# CSPS.net
KiCad netlist of a schematic drawn in Altium Designer
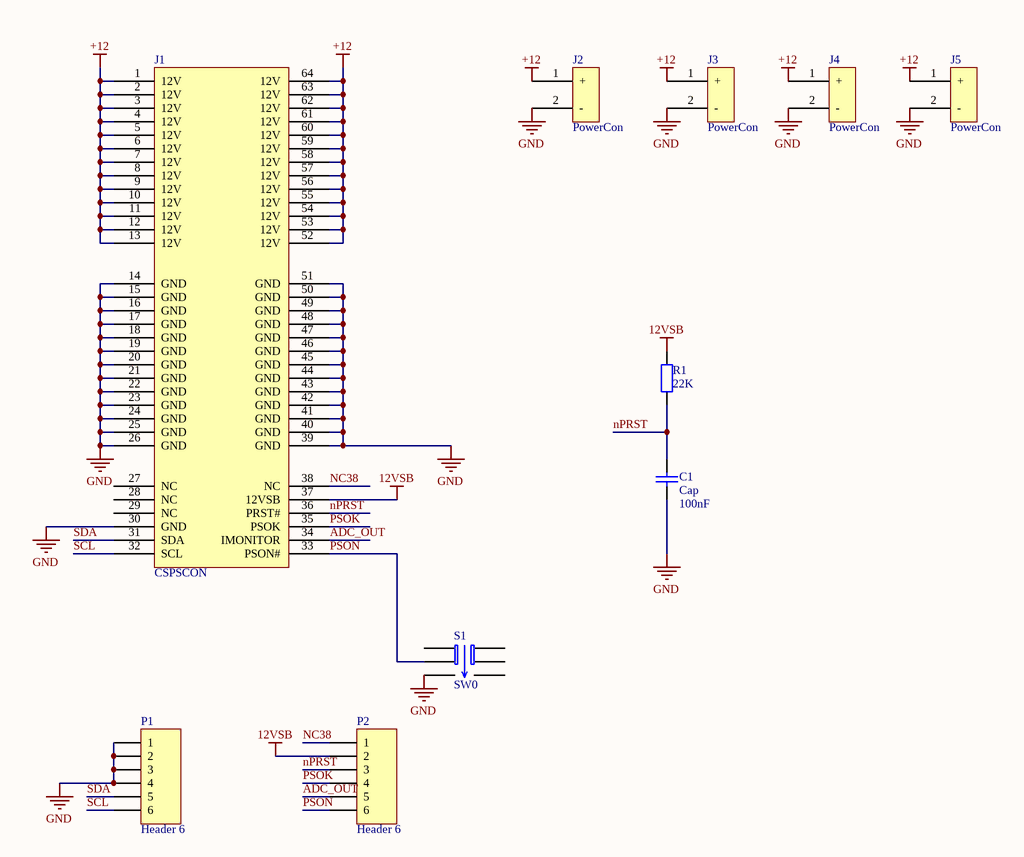
[diagram p0: CSPS.SchDoc]

(export (version "E")
  (design (tool "Eeschema 10.0.6"))
  (components
    (comp (ref "C1")
      (value "Cap")
      (footprint "0402")
      (description "Capacitor")
      (fields (field (name "ALTIUM_VALUE") "100nF") (field (name "PUBLISHER") "Altium Limited"))
      (libsource (lib "Miscellaneous Devices") (part "Cap"))
    )
    (comp (ref "J1")
      (value "CSPSCON")
      (footprint "CSPSCON2")
      (description "2.54 x 64Pin Common Slot Power Supply Connector")
      (libsource (lib "biwefc") (part "CSPSCON"))
    )
    (comp (ref "J2")
      (value "PowerCon")
      (footprint "XT60PB")
      (description "2 Pin Power Connector")
      (libsource (lib "biwefc") (part "PowerCon"))
    )
    (comp (ref "J3")
      (value "PowerCon")
      (footprint "XT60PB")
      (description "2 Pin Power Connector")
      (libsource (lib "biwefc") (part "PowerCon"))
    )
    (comp (ref "J4")
      (value "PowerCon")
      (footprint "XT60PB")
      (description "2 Pin Power Connector")
      (libsource (lib "biwefc") (part "PowerCon"))
    )
    (comp (ref "J5")
      (value "PowerCon")
      (footprint "XT60PB")
      (description "2 Pin Power Connector")
      (libsource (lib "biwefc") (part "PowerCon"))
    )
    (comp (ref "P1")
      (value "Header 6")
      (footprint "HDR1X6")
      (description "Header, 6-Pin")
      (fields (field (name "PUBLISHER") "Altium Limited"))
      (libsource (lib "Miscellaneous Connectors") (part "Header 6"))
    )
    (comp (ref "P2")
      (value "Header 6")
      (footprint "HDR1X6")
      (description "Header, 6-Pin")
      (fields (field (name "PUBLISHER") "Altium Limited"))
      (libsource (lib "Miscellaneous Connectors") (part "Header 6"))
    )
    (comp (ref "R1")
      (value "22K")
      (footprint "J1-0603")
      (description "Resistor")
      (fields (field (name "Comment") "Res2") (field (name "PUBLISHER") "Altium Limited"))
      (libsource (lib "Miscellaneous Devices") (part "Res2"))
    )
    (comp (ref "S1")
      (value "SW0")
      (footprint "SW_TH_6P-7x7")
      (description "Latching Switch.")
      (libsource (lib "biwefc") (part "SW0"))
    )
  )
  (nets
    (net (code "1") (name "+12") (class "Default")
      (node (ref "J1") (pin "1") (pinfunction "12V_1") (pintype "passive"))
      (node (ref "J1") (pin "10") (pinfunction "12V_10") (pintype "passive"))
      (node (ref "J1") (pin "11") (pinfunction "12V_11") (pintype "passive"))
      (node (ref "J1") (pin "12") (pinfunction "12V_12") (pintype "passive"))
      (node (ref "J1") (pin "13") (pinfunction "12V_13") (pintype "passive"))
      (node (ref "J1") (pin "2") (pinfunction "12V_2") (pintype "passive"))
      (node (ref "J1") (pin "3") (pinfunction "12V_3") (pintype "passive"))
      (node (ref "J1") (pin "4") (pinfunction "12V_4") (pintype "passive"))
      (node (ref "J1") (pin "5") (pinfunction "12V_5") (pintype "passive"))
      (node (ref "J1") (pin "52") (pinfunction "12V_52") (pintype "passive"))
      (node (ref "J1") (pin "53") (pinfunction "12V_53") (pintype "passive"))
      (node (ref "J1") (pin "54") (pinfunction "12V_54") (pintype "passive"))
      (node (ref "J1") (pin "55") (pinfunction "12V_55") (pintype "passive"))
      (node (ref "J1") (pin "56") (pinfunction "12V_56") (pintype "passive"))
      (node (ref "J1") (pin "57") (pinfunction "12V_57") (pintype "passive"))
      (node (ref "J1") (pin "58") (pinfunction "12V_58") (pintype "passive"))
      (node (ref "J1") (pin "59") (pinfunction "12V_59") (pintype "passive"))
      (node (ref "J1") (pin "6") (pinfunction "12V_6") (pintype "passive"))
      (node (ref "J1") (pin "60") (pinfunction "12V_60") (pintype "passive"))
      (node (ref "J1") (pin "61") (pinfunction "12V_61") (pintype "passive"))
      (node (ref "J1") (pin "62") (pinfunction "12V_62") (pintype "passive"))
      (node (ref "J1") (pin "63") (pinfunction "12V_63") (pintype "passive"))
      (node (ref "J1") (pin "64") (pinfunction "12V_64") (pintype "passive"))
      (node (ref "J1") (pin "7") (pinfunction "12V_7") (pintype "passive"))
      (node (ref "J1") (pin "8") (pinfunction "12V_8") (pintype "passive"))
      (node (ref "J1") (pin "9") (pinfunction "12V_9") (pintype "passive"))
      (node (ref "J2") (pin "1") (pinfunction "+_1") (pintype "passive"))
      (node (ref "J3") (pin "1") (pinfunction "+_1") (pintype "passive"))
      (node (ref "J4") (pin "1") (pinfunction "+_1") (pintype "passive"))
      (node (ref "J5") (pin "1") (pinfunction "+_1") (pintype "passive"))
    )
    (net (code "2") (name "/ADC_OUT") (class "Default")
      (node (ref "J1") (pin "34") (pinfunction "IMONITOR_34") (pintype "passive"))
      (node (ref "P2") (pin "5") (pinfunction "5_5") (pintype "passive"))
    )
    (net (code "3") (name "/NC38") (class "Default")
      (node (ref "J1") (pin "38") (pinfunction "NC_38") (pintype "passive"))
      (node (ref "P2") (pin "1") (pinfunction "1_1") (pintype "passive"))
    )
    (net (code "4") (name "/PSOK") (class "Default")
      (node (ref "J1") (pin "35") (pinfunction "PSOK_35") (pintype "passive"))
      (node (ref "P2") (pin "4") (pinfunction "4_4") (pintype "passive"))
    )
    (net (code "5") (name "/PSON") (class "Default")
      (node (ref "J1") (pin "33") (pinfunction "PSON#_33") (pintype "passive"))
      (node (ref "P2") (pin "6") (pinfunction "6_6") (pintype "passive"))
      (node (ref "S1") (pin "2") (pinfunction "2_2") (pintype "passive"))
    )
    (net (code "6") (name "/SCL") (class "Default")
      (node (ref "J1") (pin "32") (pinfunction "SCL_32") (pintype "passive"))
      (node (ref "P1") (pin "6") (pinfunction "6_6") (pintype "passive"))
    )
    (net (code "7") (name "/SDA") (class "Default")
      (node (ref "J1") (pin "31") (pinfunction "SDA_31") (pintype "passive"))
      (node (ref "P1") (pin "5") (pinfunction "5_5") (pintype "passive"))
    )
    (net (code "8") (name "/nPRST") (class "Default")
      (node (ref "C1") (pin "2") (pinfunction "2_2") (pintype "passive"))
      (node (ref "J1") (pin "36") (pinfunction "PRST#_36") (pintype "passive"))
      (node (ref "P2") (pin "3") (pinfunction "3_3") (pintype "passive"))
      (node (ref "R1") (pin "1") (pinfunction "1_1") (pintype "passive"))
    )
    (net (code "9") (name "12VSB") (class "Default")
      (node (ref "J1") (pin "37") (pinfunction "12VSB_37") (pintype "passive"))
      (node (ref "P2") (pin "2") (pinfunction "2_2") (pintype "passive"))
      (node (ref "R1") (pin "2") (pinfunction "2_2") (pintype "passive"))
    )
    (net (code "10") (name "GND") (class "Default")
      (node (ref "C1") (pin "1") (pinfunction "1_1") (pintype "passive"))
      (node (ref "J1") (pin "14") (pinfunction "GND_14") (pintype "passive"))
      (node (ref "J1") (pin "15") (pinfunction "GND_15") (pintype "passive"))
      (node (ref "J1") (pin "16") (pinfunction "GND_16") (pintype "passive"))
      (node (ref "J1") (pin "17") (pinfunction "GND_17") (pintype "passive"))
      (node (ref "J1") (pin "18") (pinfunction "GND_18") (pintype "passive"))
      (node (ref "J1") (pin "19") (pinfunction "GND_19") (pintype "passive"))
      (node (ref "J1") (pin "20") (pinfunction "GND_20") (pintype "passive"))
      (node (ref "J1") (pin "21") (pinfunction "GND_21") (pintype "passive"))
      (node (ref "J1") (pin "22") (pinfunction "GND_22") (pintype "passive"))
      (node (ref "J1") (pin "23") (pinfunction "GND_23") (pintype "passive"))
      (node (ref "J1") (pin "24") (pinfunction "GND_24") (pintype "passive"))
      (node (ref "J1") (pin "25") (pinfunction "GND_25") (pintype "passive"))
      (node (ref "J1") (pin "26") (pinfunction "GND_26") (pintype "passive"))
      (node (ref "J1") (pin "30") (pinfunction "GND_30") (pintype "passive"))
      (node (ref "J1") (pin "39") (pinfunction "GND_39") (pintype "passive"))
      (node (ref "J1") (pin "40") (pinfunction "GND_40") (pintype "passive"))
      (node (ref "J1") (pin "41") (pinfunction "GND_41") (pintype "passive"))
      (node (ref "J1") (pin "42") (pinfunction "GND_42") (pintype "passive"))
      (node (ref "J1") (pin "43") (pinfunction "GND_43") (pintype "passive"))
      (node (ref "J1") (pin "44") (pinfunction "GND_44") (pintype "passive"))
      (node (ref "J1") (pin "45") (pinfunction "GND_45") (pintype "passive"))
      (node (ref "J1") (pin "46") (pinfunction "GND_46") (pintype "passive"))
      (node (ref "J1") (pin "47") (pinfunction "GND_47") (pintype "passive"))
      (node (ref "J1") (pin "48") (pinfunction "GND_48") (pintype "passive"))
      (node (ref "J1") (pin "49") (pinfunction "GND_49") (pintype "passive"))
      (node (ref "J1") (pin "50") (pinfunction "GND_50") (pintype "passive"))
      (node (ref "J1") (pin "51") (pinfunction "GND_51") (pintype "passive"))
      (node (ref "J2") (pin "2") (pinfunction "-_2") (pintype "passive"))
      (node (ref "J3") (pin "2") (pinfunction "-_2") (pintype "passive"))
      (node (ref "J4") (pin "2") (pinfunction "-_2") (pintype "passive"))
      (node (ref "J5") (pin "2") (pinfunction "-_2") (pintype "passive"))
      (node (ref "P1") (pin "1") (pinfunction "1_1") (pintype "passive"))
      (node (ref "P1") (pin "2") (pinfunction "2_2") (pintype "passive"))
      (node (ref "P1") (pin "3") (pinfunction "3_3") (pintype "passive"))
      (node (ref "P1") (pin "4") (pinfunction "4_4") (pintype "passive"))
      (node (ref "S1") (pin "3") (pinfunction "3_3") (pintype "passive"))
    )
    (net (code "11") (name "unconnected-(J1-NC-Pad27)") (class "Default")
      (node (ref "J1") (pin "27") (pinfunction "NC_27") (pintype "passive"))
    )
    (net (code "12") (name "unconnected-(J1-NC-Pad28)") (class "Default")
      (node (ref "J1") (pin "28") (pinfunction "NC_28") (pintype "passive"))
    )
    (net (code "13") (name "unconnected-(J1-NC-Pad29)") (class "Default")
      (node (ref "J1") (pin "29") (pinfunction "NC_29") (pintype "passive"))
    )
    (net (code "14") (name "unconnected-(S1-2-Pad1)") (class "Default")
      (node (ref "S1") (pin "1") (pinfunction "2_1") (pintype "passive"))
    )
    (net (code "15") (name "unconnected-(S1-Pad4)") (class "Default")
      (node (ref "S1") (pin "4") (pinfunction "4_4") (pintype "passive"))
    )
    (net (code "16") (name "unconnected-(S1-Pad5)") (class "Default")
      (node (ref "S1") (pin "5") (pinfunction "5_5") (pintype "passive"))
    )
    (net (code "17") (name "unconnected-(S1-Pad6)") (class "Default")
      (node (ref "S1") (pin "6") (pinfunction "6_6") (pintype "passive"))
    )
  )
)
